# TVR_Rev2_Ignition.net
KiCad netlist of a schematic drawn in Altium Designer
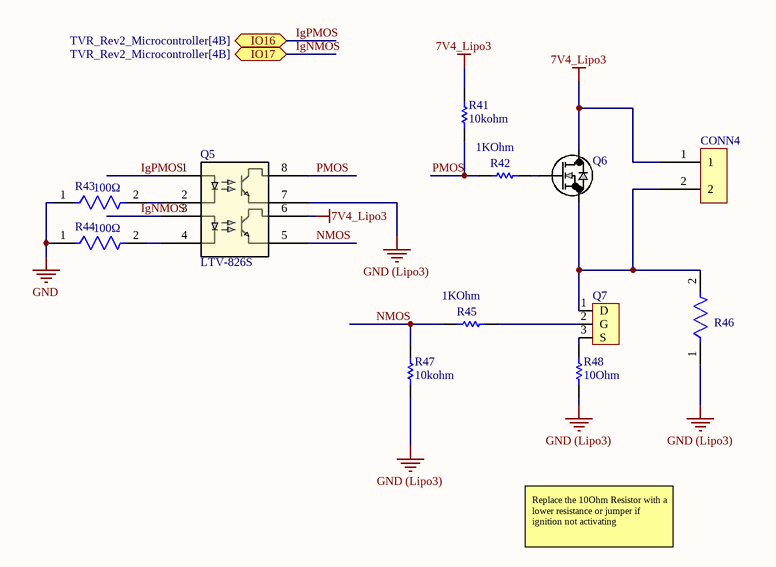
[diagram p0: TVR_Rev2_Ignition.SchDoc]

(export (version "E")
  (design (tool "Eeschema 10.0.6"))
  (components
    (comp (ref "CONN4")
      (value "691137710002")
      (footprint "2PIN_TERMINAL")
      (libsource (lib "Schlib2") (part "2PIN_TERMINAL"))
    )
    (comp (ref "Q5")
      (value "LTV-826S")
      (footprint "LTV-826S_LTO")
      (description "No Description Available")
      (libsource (lib "TVR") (part "LTV-826S"))
    )
    (comp (ref "Q6")
      (value "AOD4189")
      (footprint "TO-252_D-PAK_AOS")
      (description "P Channel MOSFET 40V 40A")
      (libsource (lib "TVR") (part "AOD4189"))
    )
    (comp (ref "Q7")
      (value "DMNH6021SK3Q-13")
      (footprint "TO252(DPAK)")
      (description "N-Channel MOSFET, 60V 50A SMD with drain pad")
      (libsource (lib "TVR") (part "DMNH6021SK3Q-13"))
    )
    (comp (ref "R41")
      (value "RC0805JR-0710KL")
      (footprint "RESC2013X60X35ML10T20")
      (description "Chip Resistor, 10 KOhm, +/- 5%, 0.125 W, -55 to 155 degC, 0805 (2012 Metric), RoHS, Tape and Reel")
      (fields (field (name "MANUFACTURER") "Yageo") (field (name "RESISTANCE") "10kohm"))
      (libsource (lib "Altium Content Vault") (part "RES-2"))
    )
    (comp (ref "R42")
      (value "RC0805FR-071KL")
      (footprint "RESC2013X60X35ML10T20")
      (description "Chip Resistor, 1 KOhm, +/- 1%, 125 mW, -55 to 155 degC, 0805 (2012 Metric), RoHS, Tape and Reel")
      (fields
        (field (name "RESISTANCE") "1KOhm")
        (field (name "TOLERANCE") "1%")
        (field (name "MANUFACTURER") "Yageo")
      )
      (libsource (lib "Altium Content Vault") (part "RES-2"))
    )
    (comp (ref "R43")
      (value "RC0603FR-07100RL")
      (footprint "FP-RC0603-0_55-MFG")
      (fields (field (name "TOLERANCE") "1%") (field (name "RESISTANCE") "100Ω"))
      (libsource (lib "Altium Content Vault") (part "1029c3af85768c4190bb7ad29bc67b5"))
    )
    (comp (ref "R44")
      (value "RC0603FR-07100RL")
      (footprint "FP-RC0603-0_55-MFG")
      (fields (field (name "TOLERANCE") "1%") (field (name "RESISTANCE") "100Ω"))
      (libsource (lib "Altium Content Vault") (part "1029c3af85768c4190bb7ad29bc67b5"))
    )
    (comp (ref "R45")
      (value "RC0805FR-071KL")
      (footprint "RESC2013X60X35ML10T20")
      (description "Chip Resistor, 1 KOhm, +/- 1%, 125 mW, -55 to 155 degC, 0805 (2012 Metric), RoHS, Tape and Reel")
      (fields
        (field (name "RESISTANCE") "1KOhm")
        (field (name "TOLERANCE") "1%")
        (field (name "MANUFACTURER") "Yageo")
      )
      (libsource (lib "Altium Content Vault") (part "RES-2"))
    )
    (comp (ref "R46")
      (value "RC0805FR-07100KL")
      (footprint "FP-RC0805-0_6-IPC_C")
      (description "RES 100K OHM 1% 1/8W 0805")
      (fields (field (name "TOLERANCE") "1%"))
      (libsource (lib "Altium Content Vault") (part "1029c3af85768c4190bb7ad29bc67b5"))
    )
    (comp (ref "R47")
      (value "RC0805JR-0710KL")
      (footprint "RESC2013X60X35ML10T20")
      (description "Chip Resistor, 10 KOhm, +/- 5%, 0.125 W, -55 to 155 degC, 0805 (2012 Metric), RoHS, Tape and Reel")
      (fields (field (name "MANUFACTURER") "Yageo") (field (name "RESISTANCE") "10kohm"))
      (libsource (lib "Altium Content Vault") (part "RES-2"))
    )
    (comp (ref "R48")
      (value "RC0805FR-0710RL")
      (footprint "RESC2013X60X35ML10T20")
      (description "Chip Resistor, 10 Ohm, +/- 1%, 0.125 W, -55 to 155 degC, 0805 (2012 Metric), RoHS, Tape and Reel")
      (fields
        (field (name "RESISTANCE") "10Ohm")
        (field (name "MANUFACTURER") "Yageo")
        (field (name "TOLERANCE") "1%")
      )
      (libsource (lib "Altium Content Vault") (part "RES-2"))
    )
  )
  (nets
    (net (code "2") (name "/IgNMOS") (class "Default")
      (node (ref "Q5") (pin "3") (pinfunction "3_3") (pintype "passive"))
    )
    (net (code "3") (name "/IgPMOS") (class "Default")
      (node (ref "Q5") (pin "1") (pinfunction "1_1") (pintype "passive"))
    )
    (net (code "4") (name "/NMOS") (class "Default")
      (node (ref "Q5") (pin "5") (pinfunction "5_5") (pintype "passive"))
      (node (ref "R45") (pin "1") (pinfunction "1_1") (pintype "passive"))
      (node (ref "R47") (pin "1") (pinfunction "1_1") (pintype "passive"))
    )
    (net (code "5") (name "/PMOS") (class "Default")
      (node (ref "Q5") (pin "8") (pinfunction "8_8") (pintype "passive"))
      (node (ref "R41") (pin "1") (pinfunction "1_1") (pintype "passive"))
      (node (ref "R42") (pin "1") (pinfunction "1_1") (pintype "passive"))
    )
    (net (code "6") (name "7V4_Lipo3") (class "Default")
      (node (ref "CONN4") (pin "1") (pinfunction "1_1") (pintype "passive"))
      (node (ref "Q5") (pin "6") (pinfunction "6_6") (pintype "passive"))
      (node (ref "Q6") (pin "3") (pinfunction "D_3") (pintype "passive"))
      (node (ref "R41") (pin "2") (pinfunction "2_2") (pintype "passive"))
    )
    (net (code "7") (name "GND") (class "Default")
      (node (ref "R43") (pin "1") (pinfunction "1_1") (pintype "passive"))
      (node (ref "R44") (pin "1") (pinfunction "1_1") (pintype "passive"))
    )
    (net (code "8") (name "GND (Lipo3)") (class "Default")
      (node (ref "Q5") (pin "7") (pinfunction "7_7") (pintype "passive"))
      (node (ref "R46") (pin "1") (pinfunction "1_1") (pintype "passive"))
      (node (ref "R47") (pin "2") (pinfunction "2_2") (pintype "passive"))
      (node (ref "R48") (pin "1") (pinfunction "1_1") (pintype "passive"))
    )
    (net (code "9") (name "Net-(Q5-Pad2)") (class "Default")
      (node (ref "Q5") (pin "2") (pinfunction "2_2") (pintype "passive"))
      (node (ref "R43") (pin "2") (pinfunction "2_2") (pintype "passive"))
    )
    (net (code "10") (name "Net-(Q5-Pad4)") (class "Default")
      (node (ref "Q5") (pin "4") (pinfunction "4_4") (pintype "passive"))
      (node (ref "R44") (pin "2") (pinfunction "2_2") (pintype "passive"))
    )
    (net (code "11") (name "Net-(Q6-G)") (class "Default")
      (node (ref "Q6") (pin "1") (pinfunction "G_1") (pintype "passive"))
      (node (ref "R42") (pin "2") (pinfunction "2_2") (pintype "passive"))
    )
    (net (code "12") (name "Net-(Q6-S)") (class "Default")
      (node (ref "CONN4") (pin "2") (pinfunction "2_2") (pintype "passive"))
      (node (ref "Q6") (pin "2") (pinfunction "S_2") (pintype "passive"))
      (node (ref "Q7") (pin "1") (pinfunction "D_1") (pintype "passive"))
      (node (ref "R46") (pin "2") (pinfunction "2_2") (pintype "passive"))
    )
    (net (code "13") (name "Net-(Q7-G)") (class "Default")
      (node (ref "Q7") (pin "2") (pinfunction "G_2") (pintype "passive"))
      (node (ref "R45") (pin "2") (pinfunction "2_2") (pintype "passive"))
    )
    (net (code "14") (name "Net-(Q7-S)") (class "Default")
      (node (ref "Q7") (pin "3") (pinfunction "S_3") (pintype "passive"))
      (node (ref "R48") (pin "2") (pinfunction "2_2") (pintype "passive"))
    )
  )
)
